# driver.net
KiCad netlist of a schematic drawn in EAGLE
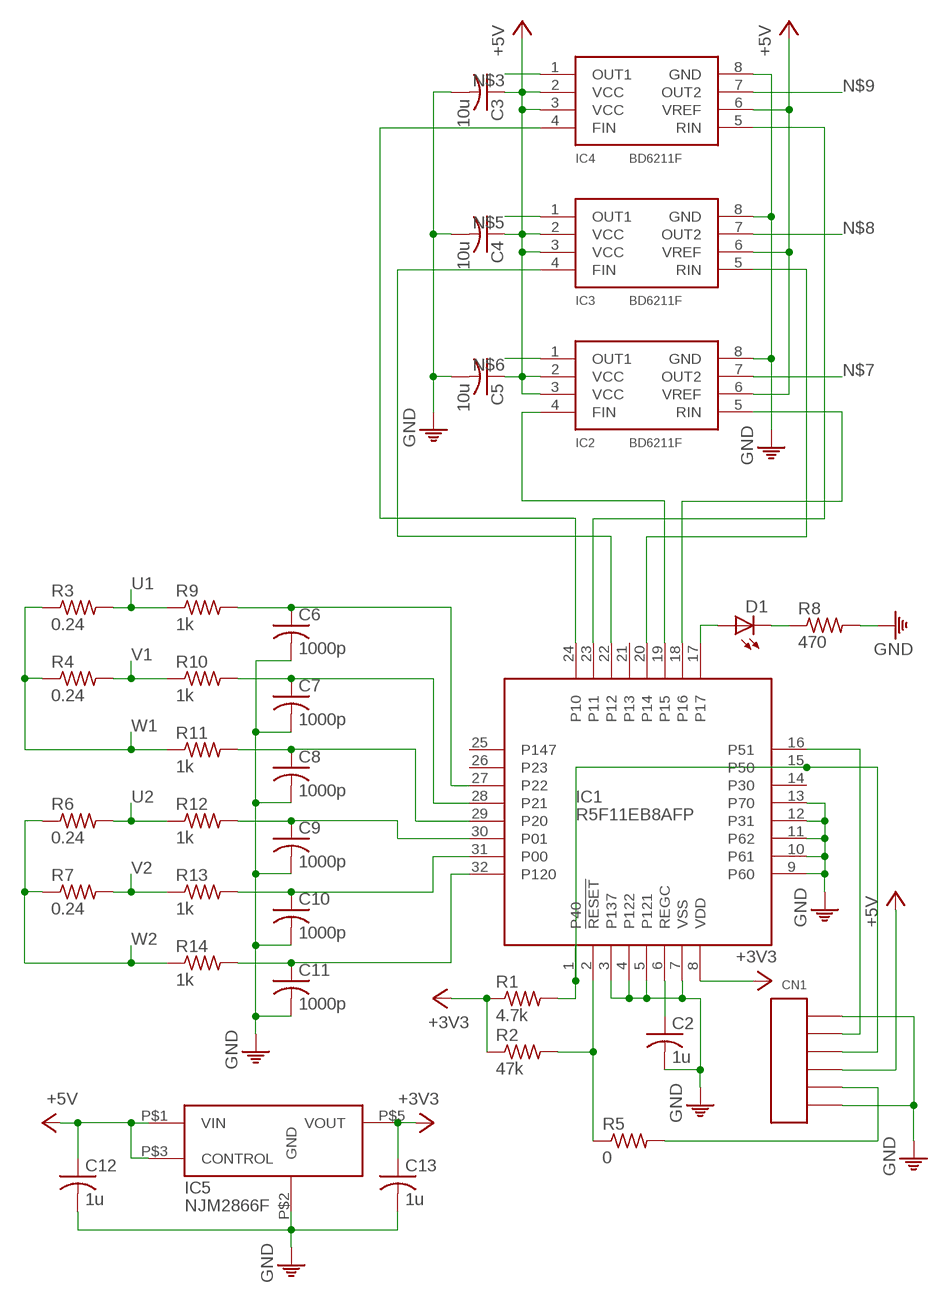
[diagram p0: schematic, sheet 1]

(export (version "E")
  (design (tool "Eeschema 10.0.6"))
  (components
    (comp (ref "C2")
      (value "1u")
      (footprint "eagle-import:C2012")
      (libsource (lib "eagle-import") (part "C2012"))
    )
    (comp (ref "C3")
      (value "10u")
      (footprint "eagle-import:C2012")
      (libsource (lib "eagle-import") (part "C2012"))
    )
    (comp (ref "C4")
      (value "10u")
      (footprint "eagle-import:C2012")
      (libsource (lib "eagle-import") (part "C2012"))
    )
    (comp (ref "C5")
      (value "10u")
      (footprint "eagle-import:C2012")
      (libsource (lib "eagle-import") (part "C2012"))
    )
    (comp (ref "C6")
      (value "1000p")
      (footprint "eagle-import:C2012")
      (libsource (lib "eagle-import") (part "C2012"))
    )
    (comp (ref "C7")
      (value "1000p")
      (footprint "eagle-import:C2012")
      (libsource (lib "eagle-import") (part "C2012"))
    )
    (comp (ref "C8")
      (value "1000p")
      (footprint "eagle-import:C2012")
      (libsource (lib "eagle-import") (part "C2012"))
    )
    (comp (ref "C9")
      (value "1000p")
      (footprint "eagle-import:C2012")
      (libsource (lib "eagle-import") (part "C2012"))
    )
    (comp (ref "C10")
      (value "1000p")
      (footprint "eagle-import:C2012")
      (libsource (lib "eagle-import") (part "C2012"))
    )
    (comp (ref "C11")
      (value "1000p")
      (footprint "eagle-import:C2012")
      (libsource (lib "eagle-import") (part "C2012"))
    )
    (comp (ref "C12")
      (value "1u")
      (footprint "eagle-import:C2012")
      (libsource (lib "eagle-import") (part "C2012"))
    )
    (comp (ref "C13")
      (value "1u")
      (footprint "eagle-import:C2012")
      (libsource (lib "eagle-import") (part "C2012"))
    )
    (comp (ref "CN1")
      (value "PH-1X06RG")
      (footprint "eagle-import:PH-1X06RG")
      (libsource (lib "eagle-import") (part "PH-1X06RG"))
    )
    (comp (ref "D1")
      (value "LED2012")
      (footprint "eagle-import:CHIP-LED0805")
      (libsource (lib "eagle-import") (part "LED2012"))
    )
    (comp (ref "IC1")
      (value "R5F11EB8AFP")
      (footprint "eagle-import:P-LQFP32-7X7-0.80")
      (libsource (lib "eagle-import") (part "R5F11EBFP8A"))
    )
    (comp (ref "IC2")
      (value "BD6211F")
      (footprint "eagle-import:SOP8")
      (libsource (lib "eagle-import") (part "BD6211F"))
    )
    (comp (ref "IC3")
      (value "BD6211F")
      (footprint "eagle-import:SOP8")
      (libsource (lib "eagle-import") (part "BD6211F"))
    )
    (comp (ref "IC4")
      (value "BD6211F")
      (footprint "eagle-import:SOP8")
      (libsource (lib "eagle-import") (part "BD6211F"))
    )
    (comp (ref "IC5")
      (value "NJM2866F")
      (footprint "eagle-import:SOT-23-5")
      (libsource (lib "eagle-import") (part "NJM2866F"))
    )
    (comp (ref "R1")
      (value "4.7k")
      (footprint "eagle-import:R2012")
      (libsource (lib "eagle-import") (part "R2012"))
    )
    (comp (ref "R2")
      (value "47k")
      (footprint "eagle-import:R2012")
      (libsource (lib "eagle-import") (part "R2012"))
    )
    (comp (ref "R3")
      (value "0.24")
      (footprint "eagle-import:R3225")
      (libsource (lib "eagle-import") (part "R3225"))
    )
    (comp (ref "R4")
      (value "0.24")
      (footprint "eagle-import:R3225")
      (libsource (lib "eagle-import") (part "R3225"))
    )
    (comp (ref "R5")
      (value "0")
      (footprint "eagle-import:R2012")
      (libsource (lib "eagle-import") (part "R2012"))
    )
    (comp (ref "R6")
      (value "0.24")
      (footprint "eagle-import:R3225")
      (libsource (lib "eagle-import") (part "R3225"))
    )
    (comp (ref "R7")
      (value "0.24")
      (footprint "eagle-import:R3225")
      (libsource (lib "eagle-import") (part "R3225"))
    )
    (comp (ref "R8")
      (value "470")
      (footprint "eagle-import:R2012")
      (libsource (lib "eagle-import") (part "R2012"))
    )
    (comp (ref "R9")
      (value "1k")
      (footprint "eagle-import:R2012")
      (libsource (lib "eagle-import") (part "R2012"))
    )
    (comp (ref "R10")
      (value "1k")
      (footprint "eagle-import:R2012")
      (libsource (lib "eagle-import") (part "R2012"))
    )
    (comp (ref "R11")
      (value "1k")
      (footprint "eagle-import:R2012")
      (libsource (lib "eagle-import") (part "R2012"))
    )
    (comp (ref "R12")
      (value "1k")
      (footprint "eagle-import:R2012")
      (libsource (lib "eagle-import") (part "R2012"))
    )
    (comp (ref "R13")
      (value "1k")
      (footprint "eagle-import:R2012")
      (libsource (lib "eagle-import") (part "R2012"))
    )
    (comp (ref "R14")
      (value "1k")
      (footprint "eagle-import:R2012")
      (libsource (lib "eagle-import") (part "R2012"))
    )
  )
  (nets
    (net (code "1") (name "+3V3") (class "Default")
      (node (ref "C13") (pin "1") (pinfunction "1_1") (pintype "passive"))
      (node (ref "IC1") (pin "8") (pinfunction "VDD_8") (pintype "power_in"))
      (node (ref "IC5") (pin "P$5") (pinfunction "VOUT_P$5") (pintype "power_in"))
      (node (ref "R1") (pin "1") (pinfunction "1_1") (pintype "passive"))
      (node (ref "R2") (pin "1") (pinfunction "1_1") (pintype "passive"))
    )
    (net (code "2") (name "+5V") (class "Default")
      (node (ref "C12") (pin "1") (pinfunction "1_1") (pintype "passive"))
      (node (ref "C3") (pin "1") (pinfunction "1_1") (pintype "passive"))
      (node (ref "C4") (pin "1") (pinfunction "1_1") (pintype "passive"))
      (node (ref "C5") (pin "1") (pinfunction "1_1") (pintype "passive"))
      (node (ref "CN1") (pin "P$3") (pinfunction "P$3_P$3") (pintype "bidirectional"))
      (node (ref "IC2") (pin "2") (pinfunction "VCC_2") (pintype "bidirectional"))
      (node (ref "IC2") (pin "3") (pinfunction "VCC_3") (pintype "bidirectional"))
      (node (ref "IC2") (pin "6") (pinfunction "VREF_6") (pintype "bidirectional"))
      (node (ref "IC3") (pin "2") (pinfunction "VCC_2") (pintype "bidirectional"))
      (node (ref "IC3") (pin "3") (pinfunction "VCC_3") (pintype "bidirectional"))
      (node (ref "IC3") (pin "6") (pinfunction "VREF_6") (pintype "bidirectional"))
      (node (ref "IC4") (pin "2") (pinfunction "VCC_2") (pintype "bidirectional"))
      (node (ref "IC4") (pin "3") (pinfunction "VCC_3") (pintype "bidirectional"))
      (node (ref "IC4") (pin "6") (pinfunction "VREF_6") (pintype "bidirectional"))
      (node (ref "IC5") (pin "P$1") (pinfunction "VIN_P$1") (pintype "input"))
      (node (ref "IC5") (pin "P$3") (pinfunction "CONTROL_P$3") (pintype "input"))
    )
    (net (code "3") (name "/N$3") (class "Default")
      (node (ref "IC4") (pin "1") (pinfunction "OUT1_1") (pintype "bidirectional"))
    )
    (net (code "4") (name "/N$5") (class "Default")
      (node (ref "IC3") (pin "1") (pinfunction "OUT1_1") (pintype "bidirectional"))
    )
    (net (code "5") (name "/N$6") (class "Default")
      (node (ref "IC2") (pin "1") (pinfunction "OUT1_1") (pintype "bidirectional"))
    )
    (net (code "6") (name "/N$7") (class "Default")
      (node (ref "IC2") (pin "7") (pinfunction "OUT2_7") (pintype "bidirectional"))
    )
    (net (code "7") (name "/N$8") (class "Default")
      (node (ref "IC3") (pin "7") (pinfunction "OUT2_7") (pintype "bidirectional"))
    )
    (net (code "8") (name "/N$9") (class "Default")
      (node (ref "IC4") (pin "7") (pinfunction "OUT2_7") (pintype "bidirectional"))
    )
    (net (code "9") (name "/U1") (class "Default")
      (node (ref "R3") (pin "2") (pinfunction "2_2") (pintype "passive"))
      (node (ref "R9") (pin "1") (pinfunction "1_1") (pintype "passive"))
    )
    (net (code "10") (name "/U2") (class "Default")
      (node (ref "R12") (pin "1") (pinfunction "1_1") (pintype "passive"))
      (node (ref "R6") (pin "2") (pinfunction "2_2") (pintype "passive"))
    )
    (net (code "11") (name "/V1") (class "Default")
      (node (ref "R10") (pin "1") (pinfunction "1_1") (pintype "passive"))
      (node (ref "R4") (pin "2") (pinfunction "2_2") (pintype "passive"))
    )
    (net (code "12") (name "/V2") (class "Default")
      (node (ref "R13") (pin "1") (pinfunction "1_1") (pintype "passive"))
      (node (ref "R7") (pin "2") (pinfunction "2_2") (pintype "passive"))
    )
    (net (code "13") (name "/W1") (class "Default")
      (node (ref "R11") (pin "1") (pinfunction "1_1") (pintype "passive"))
      (node (ref "R3") (pin "1") (pinfunction "1_1") (pintype "passive"))
      (node (ref "R4") (pin "1") (pinfunction "1_1") (pintype "passive"))
    )
    (net (code "14") (name "/W2") (class "Default")
      (node (ref "R14") (pin "1") (pinfunction "1_1") (pintype "passive"))
      (node (ref "R6") (pin "1") (pinfunction "1_1") (pintype "passive"))
      (node (ref "R7") (pin "1") (pinfunction "1_1") (pintype "passive"))
    )
    (net (code "15") (name "GND") (class "Default")
      (node (ref "C10") (pin "2") (pinfunction "2_2") (pintype "passive"))
      (node (ref "C11") (pin "2") (pinfunction "2_2") (pintype "passive"))
      (node (ref "C12") (pin "2") (pinfunction "2_2") (pintype "passive"))
      (node (ref "C13") (pin "2") (pinfunction "2_2") (pintype "passive"))
      (node (ref "C2") (pin "2") (pinfunction "2_2") (pintype "passive"))
      (node (ref "C3") (pin "2") (pinfunction "2_2") (pintype "passive"))
      (node (ref "C4") (pin "2") (pinfunction "2_2") (pintype "passive"))
      (node (ref "C5") (pin "2") (pinfunction "2_2") (pintype "passive"))
      (node (ref "C6") (pin "2") (pinfunction "2_2") (pintype "passive"))
      (node (ref "C7") (pin "2") (pinfunction "2_2") (pintype "passive"))
      (node (ref "C8") (pin "2") (pinfunction "2_2") (pintype "passive"))
      (node (ref "C9") (pin "2") (pinfunction "2_2") (pintype "passive"))
      (node (ref "CN1") (pin "P$1") (pinfunction "P$1_P$1") (pintype "bidirectional"))
      (node (ref "CN1") (pin "P$6") (pinfunction "P$6_P$6") (pintype "bidirectional"))
      (node (ref "IC1") (pin "10") (pinfunction "P61_10") (pintype "bidirectional"))
      (node (ref "IC1") (pin "11") (pinfunction "P62_11") (pintype "bidirectional"))
      (node (ref "IC1") (pin "12") (pinfunction "P31_12") (pintype "bidirectional"))
      (node (ref "IC1") (pin "13") (pinfunction "P70_13") (pintype "bidirectional"))
      (node (ref "IC1") (pin "3") (pinfunction "P137_3") (pintype "input"))
      (node (ref "IC1") (pin "4") (pinfunction "P122_4") (pintype "bidirectional"))
      (node (ref "IC1") (pin "5") (pinfunction "P121_5") (pintype "bidirectional"))
      (node (ref "IC1") (pin "7") (pinfunction "VSS_7") (pintype "power_in"))
      (node (ref "IC1") (pin "9") (pinfunction "P60_9") (pintype "bidirectional"))
      (node (ref "IC2") (pin "8") (pinfunction "GND_8") (pintype "bidirectional"))
      (node (ref "IC3") (pin "8") (pinfunction "GND_8") (pintype "bidirectional"))
      (node (ref "IC4") (pin "8") (pinfunction "GND_8") (pintype "bidirectional"))
      (node (ref "IC5") (pin "P$2") (pinfunction "GND_P$2") (pintype "power_in"))
      (node (ref "R8") (pin "2") (pinfunction "2_2") (pintype "passive"))
    )
    (net (code "16") (name "Net-(CN1-PadP$2)") (class "Default")
      (node (ref "CN1") (pin "P$2") (pinfunction "P$2_P$2") (pintype "bidirectional"))
      (node (ref "R5") (pin "2") (pinfunction "2_2") (pintype "passive"))
    )
    (net (code "17") (name "Net-(D1-PadC)") (class "Default")
      (node (ref "D1") (pin "C") (pinfunction "C_C") (pintype "passive"))
      (node (ref "R8") (pin "1") (pinfunction "1_1") (pintype "passive"))
    )
    (net (code "18") (name "Net-(IC1-P00)") (class "Default")
      (node (ref "C10") (pin "1") (pinfunction "1_1") (pintype "passive"))
      (node (ref "IC1") (pin "31") (pinfunction "P00_31") (pintype "bidirectional"))
      (node (ref "R13") (pin "2") (pinfunction "2_2") (pintype "passive"))
    )
    (net (code "19") (name "Net-(IC1-P01)") (class "Default")
      (node (ref "C9") (pin "1") (pinfunction "1_1") (pintype "passive"))
      (node (ref "IC1") (pin "30") (pinfunction "P01_30") (pintype "bidirectional"))
      (node (ref "R12") (pin "2") (pinfunction "2_2") (pintype "passive"))
    )
    (net (code "20") (name "Net-(IC1-P10)") (class "Default")
      (node (ref "IC1") (pin "24") (pinfunction "P10_24") (pintype "bidirectional"))
      (node (ref "IC4") (pin "4") (pinfunction "FIN_4") (pintype "bidirectional"))
    )
    (net (code "21") (name "Net-(IC1-P11)") (class "Default")
      (node (ref "IC1") (pin "23") (pinfunction "P11_23") (pintype "bidirectional"))
      (node (ref "IC4") (pin "5") (pinfunction "RIN_5") (pintype "bidirectional"))
    )
    (net (code "22") (name "Net-(IC1-P12)") (class "Default")
      (node (ref "IC1") (pin "22") (pinfunction "P12_22") (pintype "bidirectional"))
      (node (ref "IC3") (pin "4") (pinfunction "FIN_4") (pintype "bidirectional"))
    )
    (net (code "23") (name "Net-(IC1-P14)") (class "Default")
      (node (ref "IC1") (pin "20") (pinfunction "P14_20") (pintype "bidirectional"))
      (node (ref "IC3") (pin "5") (pinfunction "RIN_5") (pintype "bidirectional"))
    )
    (net (code "24") (name "Net-(IC1-P15)") (class "Default")
      (node (ref "IC1") (pin "19") (pinfunction "P15_19") (pintype "bidirectional"))
      (node (ref "IC2") (pin "4") (pinfunction "FIN_4") (pintype "bidirectional"))
    )
    (net (code "25") (name "Net-(IC1-P16)") (class "Default")
      (node (ref "IC1") (pin "18") (pinfunction "P16_18") (pintype "bidirectional"))
      (node (ref "IC2") (pin "5") (pinfunction "RIN_5") (pintype "bidirectional"))
    )
    (net (code "26") (name "Net-(IC1-P17)") (class "Default")
      (node (ref "D1") (pin "A") (pinfunction "A_A") (pintype "passive"))
      (node (ref "IC1") (pin "17") (pinfunction "P17_17") (pintype "bidirectional"))
    )
    (net (code "27") (name "Net-(IC1-P20)") (class "Default")
      (node (ref "C8") (pin "1") (pinfunction "1_1") (pintype "passive"))
      (node (ref "IC1") (pin "29") (pinfunction "P20_29") (pintype "bidirectional"))
      (node (ref "R11") (pin "2") (pinfunction "2_2") (pintype "passive"))
    )
    (net (code "28") (name "Net-(IC1-P21)") (class "Default")
      (node (ref "C7") (pin "1") (pinfunction "1_1") (pintype "passive"))
      (node (ref "IC1") (pin "28") (pinfunction "P21_28") (pintype "bidirectional"))
      (node (ref "R10") (pin "2") (pinfunction "2_2") (pintype "passive"))
    )
    (net (code "29") (name "Net-(IC1-P22)") (class "Default")
      (node (ref "C6") (pin "1") (pinfunction "1_1") (pintype "passive"))
      (node (ref "IC1") (pin "27") (pinfunction "P22_27") (pintype "bidirectional"))
      (node (ref "R9") (pin "2") (pinfunction "2_2") (pintype "passive"))
    )
    (net (code "30") (name "Net-(IC1-P40)") (class "Default")
      (node (ref "CN1") (pin "P$4") (pinfunction "P$4_P$4") (pintype "bidirectional"))
      (node (ref "IC1") (pin "1") (pinfunction "P40_1") (pintype "bidirectional"))
      (node (ref "IC1") (pin "15") (pinfunction "P50_15") (pintype "bidirectional"))
      (node (ref "R1") (pin "2") (pinfunction "2_2") (pintype "passive"))
    )
    (net (code "31") (name "Net-(IC1-P51)") (class "Default")
      (node (ref "CN1") (pin "P$5") (pinfunction "P$5_P$5") (pintype "bidirectional"))
      (node (ref "IC1") (pin "16") (pinfunction "P51_16") (pintype "bidirectional"))
    )
    (net (code "32") (name "Net-(IC1-P120)") (class "Default")
      (node (ref "C11") (pin "1") (pinfunction "1_1") (pintype "passive"))
      (node (ref "IC1") (pin "32") (pinfunction "P120_32") (pintype "bidirectional"))
      (node (ref "R14") (pin "2") (pinfunction "2_2") (pintype "passive"))
    )
    (net (code "33") (name "Net-(IC1-REGC)") (class "Default")
      (node (ref "C2") (pin "1") (pinfunction "1_1") (pintype "passive"))
      (node (ref "IC1") (pin "6") (pinfunction "REGC_6") (pintype "passive"))
    )
    (net (code "34") (name "Net-(IC1-~{RESET})") (class "Default")
      (node (ref "IC1") (pin "2") (pinfunction "~{RESET}_2") (pintype "input"))
      (node (ref "R2") (pin "2") (pinfunction "2_2") (pintype "passive"))
      (node (ref "R5") (pin "1") (pinfunction "1_1") (pintype "passive"))
    )
    (net (code "35") (name "unconnected-(IC1-P13-Pad21)") (class "Default")
      (node (ref "IC1") (pin "21") (pinfunction "P13_21") (pintype "bidirectional"))
    )
    (net (code "36") (name "unconnected-(IC1-P23-Pad26)") (class "Default")
      (node (ref "IC1") (pin "26") (pinfunction "P23_26") (pintype "bidirectional"))
    )
    (net (code "37") (name "unconnected-(IC1-P30-Pad14)") (class "Default")
      (node (ref "IC1") (pin "14") (pinfunction "P30_14") (pintype "bidirectional"))
    )
    (net (code "38") (name "unconnected-(IC1-P147-Pad25)") (class "Default")
      (node (ref "IC1") (pin "25") (pinfunction "P147_25") (pintype "bidirectional"))
    )
  )
)
